# 7_-_ADC_Chip.net
KiCad netlist of a schematic drawn in Altium Designer
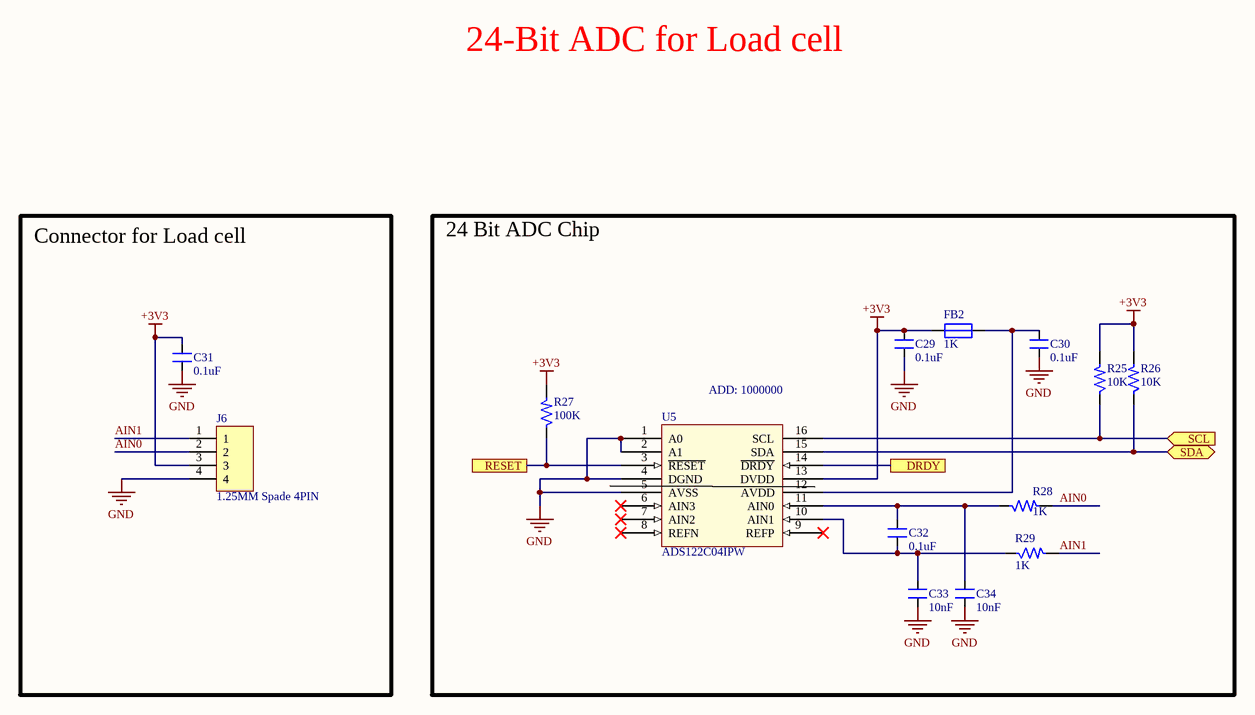
[diagram p0: [7]- ADC Chip.SchDoc]

(export (version "E")
  (design (tool "Eeschema 10.0.6"))
  (components
    (comp (ref "C29")
      (value "0.1uF")
      (footprint "CAP_0805")
      (description "0.1µF ±10% 50V Ceramic Capacitor X7R 0805 (2012 Metric)")
      (fields
        (field (name "MANUFACTURER") "Samsung")
        (field (name "MANUFACTURER PART NUMBER") "CL21B104KBCNNNC")
      )
      (libsource (lib "ESTEEMPCBLIB") (part "CAP_0.1uF-50V-10%-0805"))
    )
    (comp (ref "C30")
      (value "0.1uF")
      (footprint "CAP_0805")
      (description "0.1µF ±10% 50V Ceramic Capacitor X7R 0805 (2012 Metric)")
      (fields
        (field (name "MANUFACTURER") "Samsung")
        (field (name "MANUFACTURER PART NUMBER") "CL21B104KBCNNNC")
      )
      (libsource (lib "ESTEEMPCBLIB") (part "CAP_0.1uF-50V-10%-0805"))
    )
    (comp (ref "C31")
      (value "0.1uF")
      (footprint "CAP_0805")
      (description "0.1µF ±10% 50V Ceramic Capacitor X7R 0805 (2012 Metric)")
      (fields
        (field (name "MANUFACTURER") "Samsung")
        (field (name "MANUFACTURER PART NUMBER") "CL21B104KBCNNNC")
      )
      (libsource (lib "ESTEEMPCBLIB") (part "CAP_0.1uF-50V-10%-0805"))
    )
    (comp (ref "C32")
      (value "0.1uF")
      (footprint "CAP_0805")
      (description "0.1µF ±10% 50V Ceramic Capacitor X7R 0805 (2012 Metric)")
      (fields
        (field (name "MANUFACTURER") "Samsung")
        (field (name "MANUFACTURER PART NUMBER") "CL21B104KBCNNNC")
      )
      (libsource (lib "ESTEEMPCBLIB") (part "CAP_0.1uF-50V-10%-0805"))
    )
    (comp (ref "C33")
      (value "10nF")
      (footprint "CAP_0805")
      (description "10000pF ±10% 50V Ceramic Capacitor X7R 0805 (2012 Metric)")
      (fields
        (field (name "MANUFACTURER") "Samsung")
        (field (name "MANUFACTURER PART NUMBER") "C0805C103K5RECAUTO")
      )
      (libsource (lib "ESTEEMPCBLIB") (part "CAP_10nF-50V-10%-0805"))
    )
    (comp (ref "C34")
      (value "10nF")
      (footprint "CAP_0805")
      (description "10000pF ±10% 50V Ceramic Capacitor X7R 0805 (2012 Metric)")
      (fields
        (field (name "MANUFACTURER") "Samsung")
        (field (name "MANUFACTURER PART NUMBER") "C0805C103K5RECAUTO")
      )
      (libsource (lib "ESTEEMPCBLIB") (part "CAP_10nF-50V-10%-0805"))
    )
    (comp (ref "FB2")
      (value "1K")
      (footprint "IND_0805")
      (description "1 kOhms @ 100MHz 1 Power Line Ferrite Bead 0805 (2012 Metric) 1.6A")
      (fields
        (field (name "MANUFACTURER") "Laird")
        (field (name "MANUFACTURER PART NUMBER") "BLM21SP102SH1D")
      )
      (libsource (lib "ESTEEMPCBLIB") (part "FB_1K-100MHZ-1.6A-0805"))
    )
    (comp (ref "J6")
      (value "1.25MM Spade 4PIN")
      (footprint "CON4_50_653004117322_TH_RA")
      (description "4 Pins, 1 Row 1.25mm Pitch, right angle Connector, male")
      (fields (field (name "MANUFACTURER PART NUMBER") "653004117322") (field (name "MANUFACTURER") "JST"))
      (libsource (lib "ESTEEMPCBLIB") (part "CON-PLG_4X1-50-RA-TH"))
    )
    (comp (ref "R25")
      (value "10K")
      (footprint "RES_0603")
      (description "10 kOhms ±1% 0.1W, 1/10W Chip Resistor 0603 (1608 Metric) Automotive AEC-Q200 Thick Film")
      (fields (field (name "MANUFACTURER") "Walsin") (field (name "MANUFACTURER PART NUMBER") "WR06X1002FTL"))
      (libsource (lib "ESTEEMPCBLIB") (part "RES_10K-0.1W-1%-0603"))
    )
    (comp (ref "R26")
      (value "10K")
      (footprint "RES_0603")
      (description "10 kOhms ±1% 0.1W, 1/10W Chip Resistor 0603 (1608 Metric) Automotive AEC-Q200 Thick Film")
      (fields (field (name "MANUFACTURER") "Walsin") (field (name "MANUFACTURER PART NUMBER") "WR06X1002FTL"))
      (libsource (lib "ESTEEMPCBLIB") (part "RES_10K-0.1W-1%-0603"))
    )
    (comp (ref "R27")
      (value "100K")
      (footprint "RES_0603")
      (description "100 kOhms ±1% 0.1W, 1/10W Chip Resistor 0603 (1608 Metric) Automotive AEC-Q200 Thick Film")
      (fields
        (field (name "MANUFACTURER") "Stackpole Electronics")
        (field (name "MANUFACTURER PART NUMBER") "RMCF0603FT100K")
      )
      (libsource (lib "ESTEEMPCBLIB") (part "RES_100K-0.1W-1%-0603"))
    )
    (comp (ref "R28")
      (value "1K")
      (footprint "RES_0603")
      (description "1 kOhms ±1% 0.1W, 1/10W Chip Resistor 0603 (1608 Metric) Automotive AEC-Q200 Thick Film")
      (fields (field (name "MANUFACTURER") "Walsin") (field (name "MANUFACTURER PART NUMBER") "WR06X1001FTL"))
      (libsource (lib "ESTEEMPCBLIB") (part "RES_1K-0.1W-1%-0603"))
    )
    (comp (ref "R29")
      (value "1K")
      (footprint "RES_0603")
      (description "1 kOhms ±1% 0.1W, 1/10W Chip Resistor 0603 (1608 Metric) Automotive AEC-Q200 Thick Film")
      (fields (field (name "MANUFACTURER") "Walsin") (field (name "MANUFACTURER PART NUMBER") "WR06X1001FTL"))
      (libsource (lib "ESTEEMPCBLIB") (part "RES_1K-0.1W-1%-0603"))
    )
    (comp (ref "U5")
      (value "ADS122C04IPW")
      (footprint "TSSOP16_25-59_294_54X14_SMT")
      (description "24 Bit Analog to Digital Converter 4 Input 1 Sigma-Delta 16-TSSOP")
      (fields (field (name "MANUFACTURER") "Texas Instruments"))
      (libsource (lib "ESTEEMPCBLIB") (part "IC_ADS122C04IPW"))
    )
  )
  (nets
    (net (code "1") (name "+3V3") (class "Default")
      (node (ref "C29") (pin "2") (pinfunction "2_2") (pintype "passive"))
      (node (ref "C31") (pin "2") (pinfunction "2_2") (pintype "passive"))
      (node (ref "FB2") (pin "1") (pinfunction "1_1") (pintype "passive"))
      (node (ref "J6") (pin "3") (pinfunction "3_3") (pintype "passive"))
      (node (ref "R25") (pin "2") (pinfunction "2_2") (pintype "passive"))
      (node (ref "R26") (pin "2") (pinfunction "2_2") (pintype "passive"))
      (node (ref "R27") (pin "2") (pinfunction "2_2") (pintype "passive"))
      (node (ref "U5") (pin "13") (pinfunction "DVDD_13") (pintype "power_in"))
    )
    (net (code "2") (name "/AIN0") (class "Default")
      (node (ref "J6") (pin "2") (pinfunction "2_2") (pintype "passive"))
      (node (ref "R28") (pin "2") (pinfunction "2_2") (pintype "passive"))
    )
    (net (code "3") (name "/AIN1") (class "Default")
      (node (ref "J6") (pin "1") (pinfunction "1_1") (pintype "passive"))
      (node (ref "R29") (pin "2") (pinfunction "2_2") (pintype "passive"))
    )
    (net (code "4") (name "/DRDY") (class "Default")
      (node (ref "U5") (pin "14") (pinfunction "DRDY_14") (pintype "input"))
    )
    (net (code "5") (name "/RESET") (class "Default")
      (node (ref "R27") (pin "1") (pinfunction "1_1") (pintype "passive"))
      (node (ref "U5") (pin "3") (pinfunction "RESET_3") (pintype "input"))
    )
    (net (code "6") (name "/SCL") (class "Default")
      (node (ref "R25") (pin "1") (pinfunction "1_1") (pintype "passive"))
      (node (ref "U5") (pin "16") (pinfunction "SCL_16") (pintype "open_collector"))
    )
    (net (code "7") (name "/SDA") (class "Default")
      (node (ref "R26") (pin "1") (pinfunction "1_1") (pintype "passive"))
      (node (ref "U5") (pin "15") (pinfunction "SDA_15") (pintype "open_collector"))
    )
    (net (code "8") (name "GND") (class "Default")
      (node (ref "C29") (pin "1") (pinfunction "1_1") (pintype "passive"))
      (node (ref "C30") (pin "1") (pinfunction "1_1") (pintype "passive"))
      (node (ref "C31") (pin "1") (pinfunction "1_1") (pintype "passive"))
      (node (ref "C33") (pin "1") (pinfunction "1_1") (pintype "passive"))
      (node (ref "C34") (pin "1") (pinfunction "1_1") (pintype "passive"))
      (node (ref "J6") (pin "4") (pinfunction "4_4") (pintype "passive"))
      (node (ref "U5") (pin "1") (pinfunction "A0_1") (pintype "passive"))
      (node (ref "U5") (pin "2") (pinfunction "A1_2") (pintype "passive"))
      (node (ref "U5") (pin "4") (pinfunction "DGND_4") (pintype "power_in"))
      (node (ref "U5") (pin "5") (pinfunction "AVSS_5") (pintype "power_in"))
    )
    (net (code "9") (name "Net-(U5-AIN0)") (class "Default")
      (node (ref "C32") (pin "2") (pinfunction "2_2") (pintype "passive"))
      (node (ref "C34") (pin "2") (pinfunction "2_2") (pintype "passive"))
      (node (ref "R28") (pin "1") (pinfunction "1_1") (pintype "passive"))
      (node (ref "U5") (pin "11") (pinfunction "AIN0_11") (pintype "input"))
    )
    (net (code "10") (name "Net-(U5-AIN1)") (class "Default")
      (node (ref "C32") (pin "1") (pinfunction "1_1") (pintype "passive"))
      (node (ref "C33") (pin "2") (pinfunction "2_2") (pintype "passive"))
      (node (ref "R29") (pin "1") (pinfunction "1_1") (pintype "passive"))
      (node (ref "U5") (pin "10") (pinfunction "AIN1_10") (pintype "input"))
    )
    (net (code "11") (name "Net-(U5-AVDD)") (class "Default")
      (node (ref "C30") (pin "2") (pinfunction "2_2") (pintype "passive"))
      (node (ref "FB2") (pin "2") (pinfunction "2_2") (pintype "passive"))
      (node (ref "U5") (pin "12") (pinfunction "AVDD_12") (pintype "power_in"))
    )
    (net (code "12") (name "unconnected-(U5-AIN2-Pad7)") (class "Default")
      (node (ref "U5") (pin "7") (pinfunction "AIN2_7") (pintype "input+no_connect"))
    )
    (net (code "13") (name "unconnected-(U5-AIN3-Pad6)") (class "Default")
      (node (ref "U5") (pin "6") (pinfunction "AIN3_6") (pintype "input+no_connect"))
    )
    (net (code "14") (name "unconnected-(U5-REFN-Pad8)") (class "Default")
      (node (ref "U5") (pin "8") (pinfunction "REFN_8") (pintype "input+no_connect"))
    )
    (net (code "15") (name "unconnected-(U5-REFP-Pad9)") (class "Default")
      (node (ref "U5") (pin "9") (pinfunction "REFP_9") (pintype "input+no_connect"))
    )
  )
)
